# design.net
KiCad netlist of a schematic drawn in EasyEDA
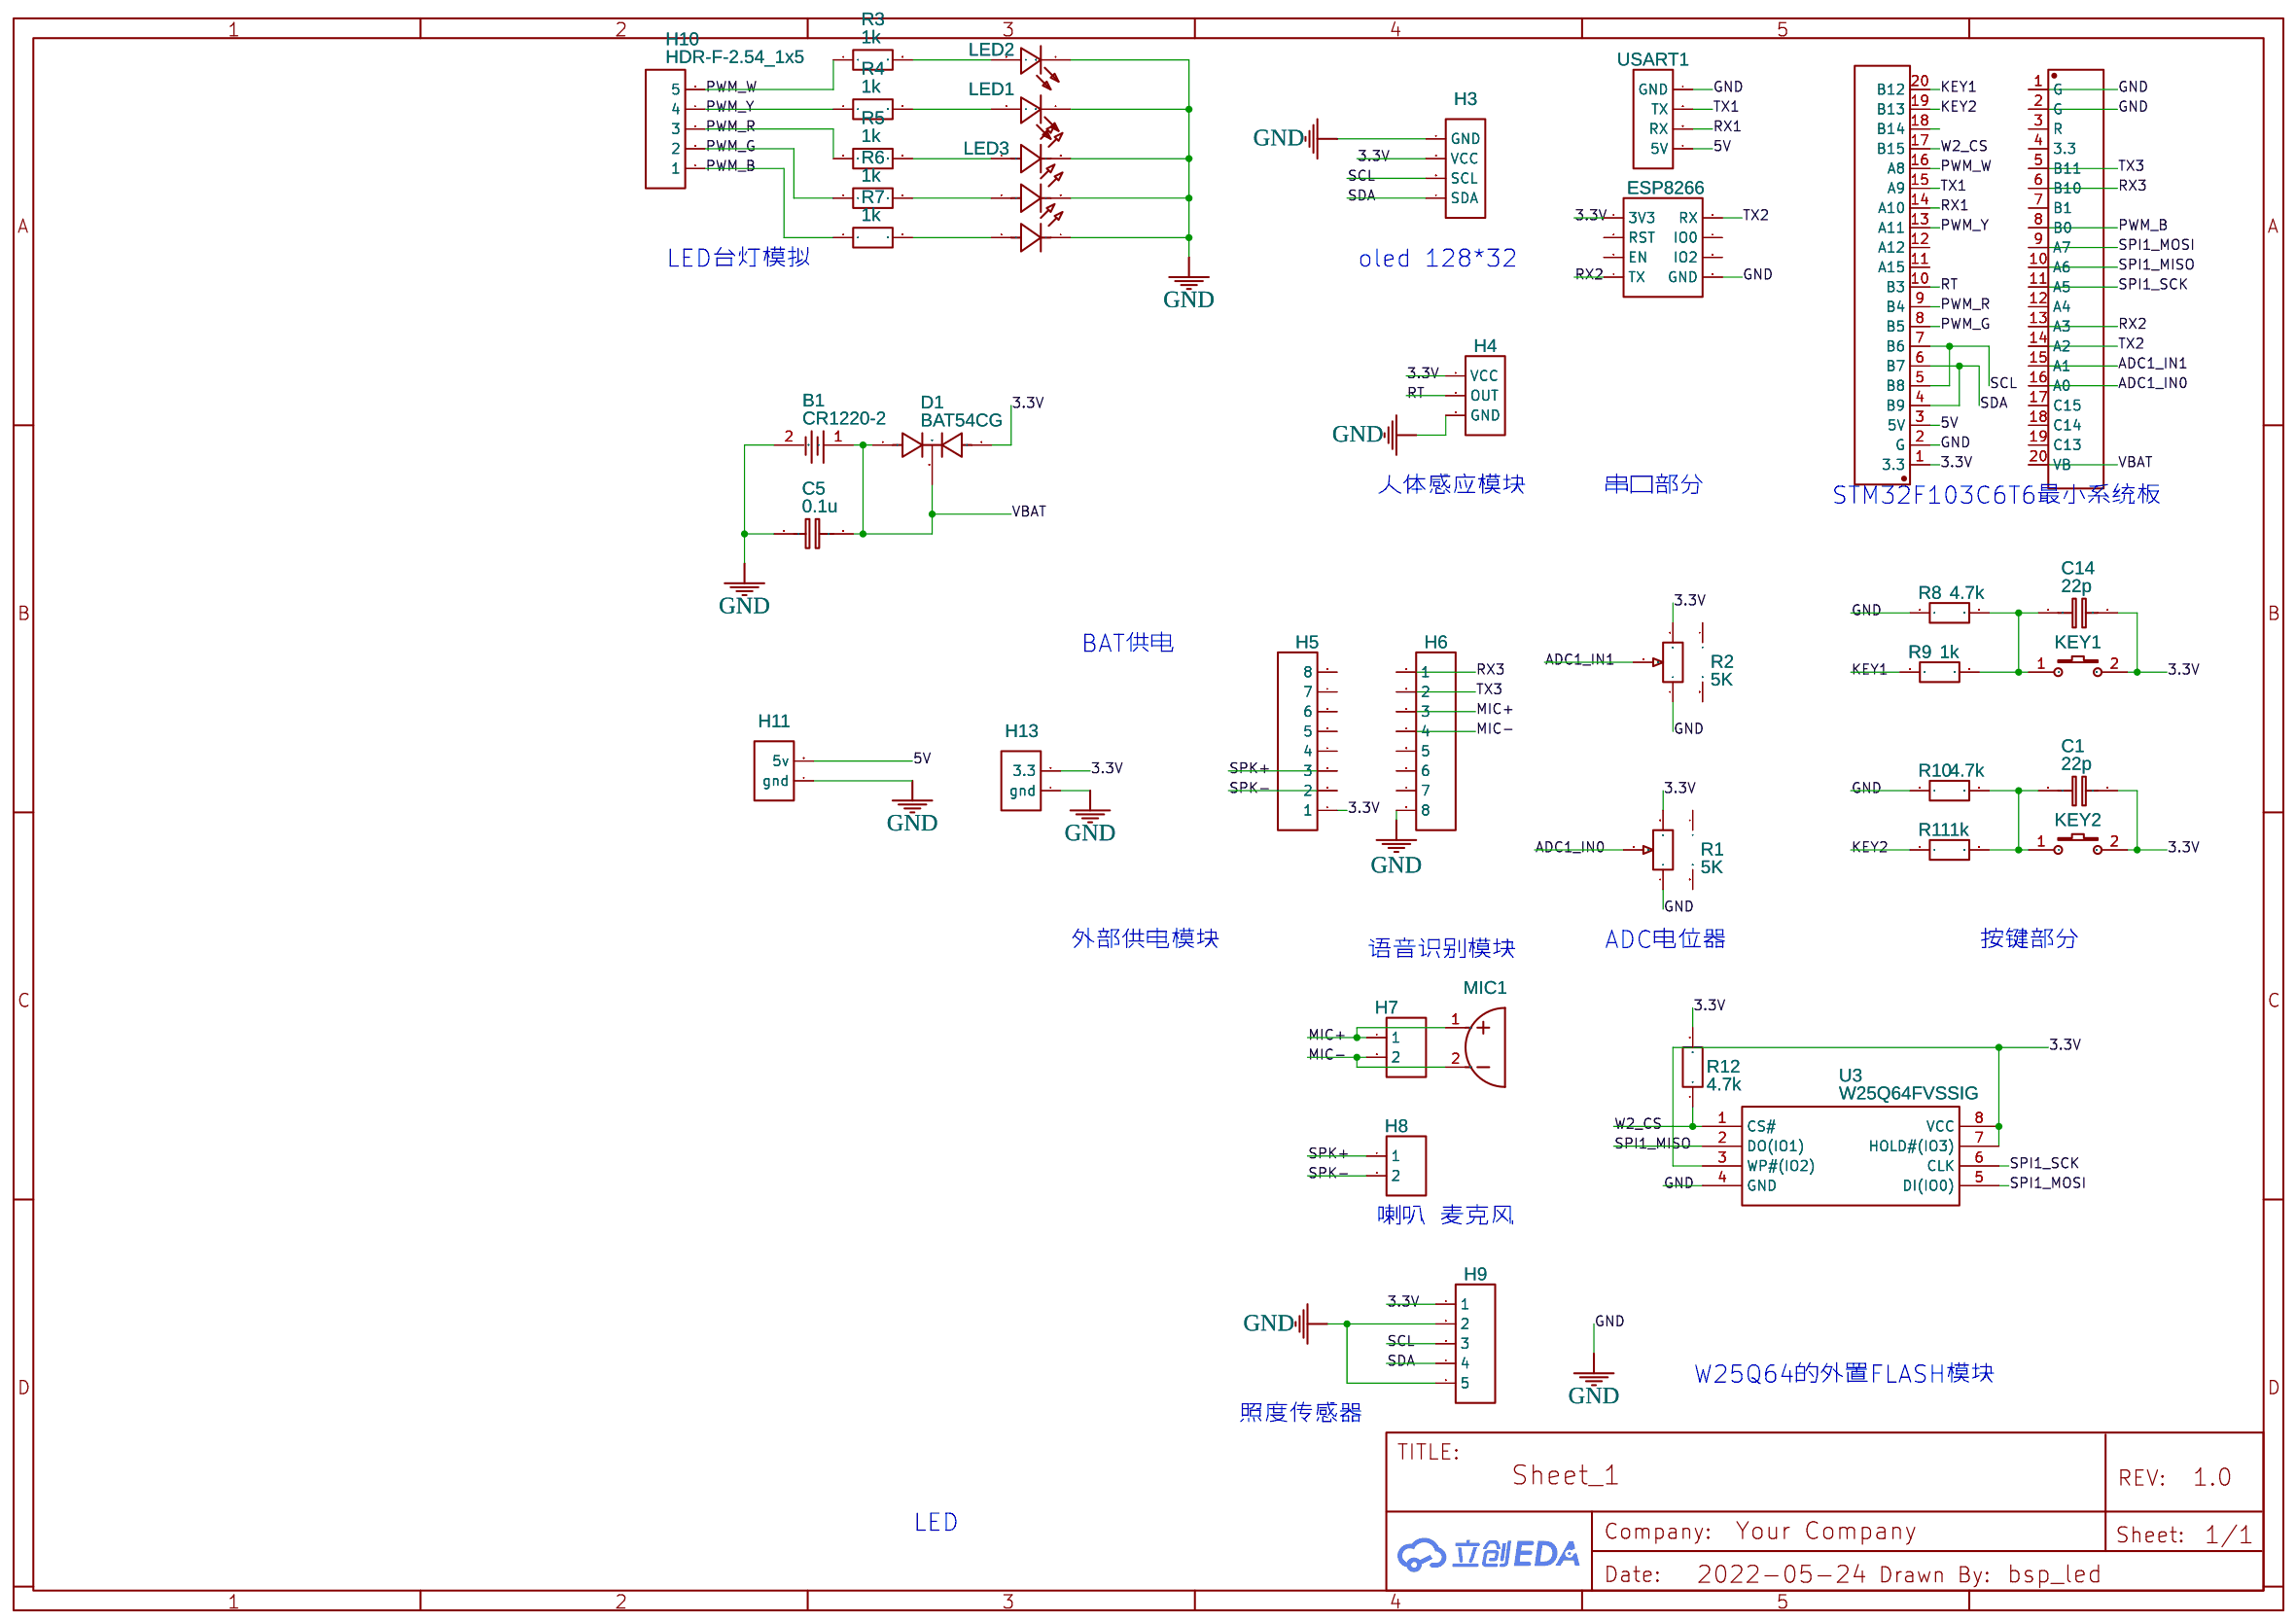
[diagram p0: schematic sheet]

(export (version "E")
  (design (tool "Eeschema 10.0.6"))
  (components
    (comp (ref "B1")
      (value "CR1220-2")
      (fields (field (name "BOM_Supplier Part") "C70381"))
      (libsource (lib "") (part "CR1220-2"))
    )
    (comp (ref "C1") (value "22p") (libsource (lib "") (part "C_1206_EU_2")))
    (comp (ref "C5") (value "0.1u") (libsource (lib "") (part "C_1206_EU_1")))
    (comp (ref "C14") (value "22p") (libsource (lib "") (part "C_1206_EU")))
    (comp (ref "D1")
      (value "BAT54CG")
      (fields (field (name "BOM_Supplier Part") "C393559"))
      (libsource (lib "") (part "BAT54CG"))
    )
    (comp (ref "ESP8266")
      (value "HDR-F-2.54_2x4")
      (fields (field (name "BOM_Supplier Part") "C239344"))
      (libsource (lib "") (part "HDR-F-2.54_2x4"))
    )
    (comp (ref "H1")
      (value "2")
      (fields
        (field (name "BOM_Manufacturer Part") "220S-1*20P H=8.5MM Ytype Gold-plated")
        (field (name "BOM_Supplier Part") "C124410")
      )
      (libsource (lib "") (part "220S-1*20P H=8.5MM Ytype Gold-plated"))
    )
    (comp (ref "H2")
      (value "1")
      (fields
        (field (name "BOM_Manufacturer Part") "220S-1*20P H=8.5MM Ytype Gold-plated")
        (field (name "BOM_Supplier Part") "C124410")
      )
      (libsource (lib "") (part "220S-1*20P H=8.5MM Ytype Gold-plated_1"))
    )
    (comp (ref "H3")
      (value "HDR-F-2.54_1x4")
      (fields (field (name "BOM_Supplier Part") "C225501"))
      (libsource (lib "") (part "HDR-F-2.54_1x4_1"))
    )
    (comp (ref "H4")
      (value "HDR-F-2.54_1x3")
      (fields (field (name "BOM_Supplier Part") "C146690"))
      (libsource (lib "") (part "HDR-F-2.54_1x3"))
    )
    (comp (ref "H5")
      (value "HDR-F-2.54_1x8")
      (fields (field (name "BOM_Supplier Part") "C225505"))
      (libsource (lib "") (part "HDR-F-2.54_1x8"))
    )
    (comp (ref "H6")
      (value "HDR-F-2.54_1x8")
      (fields (field (name "BOM_Supplier Part") "C225505"))
      (libsource (lib "") (part "HDR-F-2.54_1x8_1"))
    )
    (comp (ref "H7")
      (value "HDR-F-2.54_1x2")
      (fields (field (name "BOM_Supplier Part") "C49661"))
      (libsource (lib "") (part "HDR-F-2.54_1x2_1"))
    )
    (comp (ref "H8")
      (value "HDR-F-2.54_1x2")
      (fields (field (name "BOM_Supplier Part") "C49661"))
      (libsource (lib "") (part "HDR-F-2.54_1x2_1"))
    )
    (comp (ref "H9")
      (value "HDR-F-2.54_1x5")
      (fields (field (name "BOM_Supplier Part") "C50950"))
      (libsource (lib "") (part "HDR-F-2.54_1x5"))
    )
    (comp (ref "H10")
      (value "HDR-F-2.54_1x5")
      (fields (field (name "BOM_Supplier Part") "C50950"))
      (libsource (lib "") (part "HDR-F-2.54_1x5_1"))
    )
    (comp (ref "H11")
      (value "HDR-F-2.54_1x2")
      (fields (field (name "BOM_Supplier Part") "C49661"))
      (libsource (lib "") (part "HDR-F-2.54_1x2_2"))
    )
    (comp (ref "H13")
      (value "HDR-F-2.54_1x2")
      (fields (field (name "BOM_Supplier Part") "C49661"))
      (libsource (lib "") (part "HDR-F-2.54_1x2"))
    )
    (comp (ref "KEY1")
      (value "K2-3.6×6.1_SMD")
      (fields
        (field (name "BOM_Manufacturer Part") "K2-1107ST-A4SW-06")
        (field (name "BOM_Supplier Part") "C118141")
      )
      (libsource (lib "") (part "K2-3.6×6.1_SMD"))
    )
    (comp (ref "KEY2")
      (value "K2-3.6×6.1_SMD")
      (fields
        (field (name "BOM_Manufacturer Part") "K2-1107ST-A4SW-06")
        (field (name "BOM_Supplier Part") "C118141")
      )
      (libsource (lib "") (part "K2-3.6×6.1_SMD"))
    )
    (comp (ref "LED1")
      (value "2835正白光0.5W")
      (fields (field (name "BOM_Supplier Part") "C2895090"))
      (libsource (lib "") (part "2835正白光0.5W"))
    )
    (comp (ref "LED2")
      (value "2835正白光0.5W")
      (fields (field (name "BOM_Supplier Part") "C2895090"))
      (libsource (lib "") (part "2835正白光0.5W"))
    )
    (comp (ref "LED3")
      (value "TC5050RGBF08-3CJH-AF53A")
      (fields (field (name "BOM_Supplier Part") "C784540"))
      (libsource (lib "") (part "TC5050RGBF08-3CJH-AF53A"))
    )
    (comp (ref "MIC1")
      (value "GMI4015P-30DB")
      (fields (field (name "BOM_Supplier Part") "C529894"))
      (libsource (lib "") (part "GMI4015P-30DB"))
    )
    (comp (ref "R1")
      (value "5K")
      (fields
        (field (name "BOM_Manufacturer Part") "Potentiometer WH160-1-104")
        (field (name "BOM_Supplier Part") "C61836")
      )
      (libsource (lib "") (part "Potentiometer WH160-1-104"))
    )
    (comp (ref "R2")
      (value "5K")
      (fields
        (field (name "BOM_Manufacturer Part") "Potentiometer WH160-1-104")
        (field (name "BOM_Supplier Part") "C61836")
      )
      (libsource (lib "") (part "Potentiometer WH160-1-104"))
    )
    (comp (ref "R3") (value "1k") (libsource (lib "") (part "R_0805_EU_1")))
    (comp (ref "R4") (value "1k") (libsource (lib "") (part "R_0805_EU_1")))
    (comp (ref "R5") (value "1k") (libsource (lib "") (part "R_0805_EU_1")))
    (comp (ref "R6") (value "1k") (libsource (lib "") (part "R_0805_EU_1")))
    (comp (ref "R7") (value "1k") (libsource (lib "") (part "R_0805_EU_1")))
    (comp (ref "R8") (value "4.7k") (libsource (lib "") (part "R_0805_EU_1")))
    (comp (ref "R9") (value "1k") (libsource (lib "") (part "R_0805_EU_1")))
    (comp (ref "R10") (value "4.7k") (libsource (lib "") (part "R_0805_EU_1")))
    (comp (ref "R11") (value "1k") (libsource (lib "") (part "R_0805_EU_1")))
    (comp (ref "R12") (value "4.7k") (libsource (lib "") (part "R_0805_EU")))
    (comp (ref "U3")
      (value "W25Q64FVSSIG")
      (fields (field (name "BOM_Supplier Part") "C14067"))
      (libsource (lib "") (part "W25Q64FVSSIG"))
    )
    (comp (ref "USART1")
      (value "HDR-F-2.54_1x4")
      (fields (field (name "BOM_Supplier Part") "C225501"))
      (libsource (lib "") (part "HDR-F-2.54_1x4"))
    )
  )
  (nets
    (net (code "1") (name "/3.3V") (class "Default")
      (node (ref "C1") (pin "1") (pinfunction "1_1") (pintype "unspecified"))
      (node (ref "C14") (pin "1") (pinfunction "1_1") (pintype "unspecified"))
      (node (ref "D1") (pin "2") (pinfunction "A_2") (pintype "unspecified"))
      (node (ref "ESP8266") (pin "1") (pinfunction "3V3_1") (pintype "unspecified"))
      (node (ref "H13") (pin "2") (pinfunction "3.3_2") (pintype "input"))
      (node (ref "H2") (pin "1") (pinfunction "3.3_1") (pintype "unspecified"))
      (node (ref "H3") (pin "2") (pinfunction "VCC_2") (pintype "unspecified"))
      (node (ref "H4") (pin "1") (pinfunction "VCC_1") (pintype "input"))
      (node (ref "H5") (pin "1") (pinfunction "1_1") (pintype "unspecified"))
      (node (ref "H9") (pin "1") (pinfunction "1_1") (pintype "unspecified"))
      (node (ref "KEY1") (pin "2") (pinfunction "2_2") (pintype "unspecified"))
      (node (ref "KEY2") (pin "2") (pinfunction "2_2") (pintype "unspecified"))
      (node (ref "R1") (pin "3") (pinfunction "3_3") (pintype "input"))
      (node (ref "R12") (pin "2") (pinfunction "2_2") (pintype "unspecified"))
      (node (ref "R2") (pin "3") (pinfunction "3_3") (pintype "input"))
      (node (ref "U3") (pin "3") (pinfunction "WP#(IO2)_3") (pintype "unspecified"))
      (node (ref "U3") (pin "7") (pinfunction "HOLD#(IO3)_7") (pintype "unspecified"))
      (node (ref "U3") (pin "8") (pinfunction "VCC_8") (pintype "unspecified"))
    )
    (net (code "2") (name "/5V") (class "Default")
      (node (ref "H11") (pin "2") (pinfunction "5v_2") (pintype "input"))
      (node (ref "H2") (pin "3") (pinfunction "5V_3") (pintype "unspecified"))
      (node (ref "USART1") (pin "1") (pinfunction "5V_1") (pintype "unspecified"))
    )
    (net (code "3") (name "/ADC1_IN0") (class "Default")
      (node (ref "H1") (pin "16") (pinfunction "A0_16") (pintype "unspecified"))
      (node (ref "R1") (pin "2") (pinfunction "2_2") (pintype "input"))
    )
    (net (code "4") (name "/ADC1_IN1") (class "Default")
      (node (ref "H1") (pin "15") (pinfunction "A1_15") (pintype "unspecified"))
      (node (ref "R2") (pin "2") (pinfunction "2_2") (pintype "input"))
    )
    (net (code "5") (name "/KEY1") (class "Default")
      (node (ref "H2") (pin "20") (pinfunction "B12_20") (pintype "unspecified"))
      (node (ref "R9") (pin "1") (pinfunction "1_1") (pintype "unspecified"))
    )
    (net (code "6") (name "/KEY2") (class "Default")
      (node (ref "H2") (pin "19") (pinfunction "B13_19") (pintype "unspecified"))
      (node (ref "R11") (pin "1") (pinfunction "1_1") (pintype "unspecified"))
    )
    (net (code "7") (name "/MIC+") (class "Default")
      (node (ref "H6") (pin "3") (pinfunction "3_3") (pintype "unspecified"))
      (node (ref "H7") (pin "1") (pinfunction "1_1") (pintype "input"))
      (node (ref "MIC1") (pin "1") (pinfunction "1_1") (pintype "unspecified"))
    )
    (net (code "8") (name "/MIC-") (class "Default")
      (node (ref "H6") (pin "4") (pinfunction "4_4") (pintype "unspecified"))
      (node (ref "H7") (pin "2") (pinfunction "2_2") (pintype "input"))
      (node (ref "MIC1") (pin "2") (pinfunction "2_2") (pintype "unspecified"))
    )
    (net (code "9") (name "/PWM_B") (class "Default")
      (node (ref "H1") (pin "8") (pinfunction "B0_8") (pintype "unspecified"))
      (node (ref "H10") (pin "1") (pinfunction "1_1") (pintype "unspecified"))
      (node (ref "R7") (pin "1") (pinfunction "1_1") (pintype "unspecified"))
    )
    (net (code "10") (name "/PWM_G") (class "Default")
      (node (ref "H10") (pin "2") (pinfunction "2_2") (pintype "unspecified"))
      (node (ref "H2") (pin "8") (pinfunction "B5_8") (pintype "unspecified"))
      (node (ref "R6") (pin "1") (pinfunction "1_1") (pintype "unspecified"))
    )
    (net (code "11") (name "/PWM_R") (class "Default")
      (node (ref "H10") (pin "3") (pinfunction "3_3") (pintype "unspecified"))
      (node (ref "H2") (pin "9") (pinfunction "B4_9") (pintype "unspecified"))
      (node (ref "R5") (pin "1") (pinfunction "1_1") (pintype "unspecified"))
    )
    (net (code "12") (name "/PWM_W") (class "Default")
      (node (ref "H10") (pin "5") (pinfunction "5_5") (pintype "unspecified"))
      (node (ref "H2") (pin "16") (pinfunction "A8_16") (pintype "unspecified"))
      (node (ref "R3") (pin "1") (pinfunction "1_1") (pintype "unspecified"))
    )
    (net (code "13") (name "/PWM_Y") (class "Default")
      (node (ref "H10") (pin "4") (pinfunction "4_4") (pintype "unspecified"))
      (node (ref "H2") (pin "13") (pinfunction "A11_13") (pintype "unspecified"))
      (node (ref "R4") (pin "1") (pinfunction "1_1") (pintype "unspecified"))
    )
    (net (code "14") (name "/RT") (class "Default")
      (node (ref "H2") (pin "10") (pinfunction "B3_10") (pintype "unspecified"))
      (node (ref "H4") (pin "2") (pinfunction "OUT_2") (pintype "input"))
    )
    (net (code "15") (name "/RX1") (class "Default")
      (node (ref "H2") (pin "14") (pinfunction "A10_14") (pintype "unspecified"))
      (node (ref "USART1") (pin "2") (pinfunction "RX_2") (pintype "unspecified"))
    )
    (net (code "16") (name "/RX2") (class "Default")
      (node (ref "ESP8266") (pin "7") (pinfunction "TX_7") (pintype "unspecified"))
      (node (ref "H1") (pin "13") (pinfunction "A3_13") (pintype "unspecified"))
    )
    (net (code "17") (name "/RX3") (class "Default")
      (node (ref "H1") (pin "6") (pinfunction "B10_6") (pintype "unspecified"))
      (node (ref "H6") (pin "1") (pinfunction "1_1") (pintype "unspecified"))
    )
    (net (code "18") (name "/SCL") (class "Default")
      (node (ref "H2") (pin "5") (pinfunction "B8_5") (pintype "unspecified"))
      (node (ref "H2") (pin "7") (pinfunction "B6_7") (pintype "unspecified"))
      (node (ref "H3") (pin "3") (pinfunction "SCL_3") (pintype "unspecified"))
      (node (ref "H9") (pin "3") (pinfunction "3_3") (pintype "unspecified"))
    )
    (net (code "19") (name "/SDA") (class "Default")
      (node (ref "H2") (pin "4") (pinfunction "B9_4") (pintype "unspecified"))
      (node (ref "H2") (pin "6") (pinfunction "B7_6") (pintype "unspecified"))
      (node (ref "H3") (pin "4") (pinfunction "SDA_4") (pintype "unspecified"))
      (node (ref "H9") (pin "4") (pinfunction "4_4") (pintype "unspecified"))
    )
    (net (code "20") (name "/SPI1_MISO") (class "Default")
      (node (ref "H1") (pin "10") (pinfunction "A6_10") (pintype "unspecified"))
      (node (ref "U3") (pin "2") (pinfunction "DO(IO1)_2") (pintype "unspecified"))
    )
    (net (code "21") (name "/SPI1_MOSI") (class "Default")
      (node (ref "H1") (pin "9") (pinfunction "A7_9") (pintype "unspecified"))
      (node (ref "U3") (pin "5") (pinfunction "DI(IO0)_5") (pintype "unspecified"))
    )
    (net (code "22") (name "/SPI1_SCK") (class "Default")
      (node (ref "H1") (pin "11") (pinfunction "A5_11") (pintype "unspecified"))
      (node (ref "U3") (pin "6") (pinfunction "CLK_6") (pintype "unspecified"))
    )
    (net (code "23") (name "/SPK+") (class "Default")
      (node (ref "H5") (pin "3") (pinfunction "3_3") (pintype "unspecified"))
      (node (ref "H8") (pin "1") (pinfunction "1_1") (pintype "input"))
    )
    (net (code "24") (name "/SPK-") (class "Default")
      (node (ref "H5") (pin "2") (pinfunction "2_2") (pintype "unspecified"))
      (node (ref "H8") (pin "2") (pinfunction "2_2") (pintype "input"))
    )
    (net (code "25") (name "/TX1") (class "Default")
      (node (ref "H2") (pin "15") (pinfunction "A9_15") (pintype "unspecified"))
      (node (ref "USART1") (pin "3") (pinfunction "TX_3") (pintype "unspecified"))
    )
    (net (code "26") (name "/TX2") (class "Default")
      (node (ref "ESP8266") (pin "2") (pinfunction "RX_2") (pintype "unspecified"))
      (node (ref "H1") (pin "14") (pinfunction "A2_14") (pintype "unspecified"))
    )
    (net (code "27") (name "/TX3") (class "Default")
      (node (ref "H1") (pin "5") (pinfunction "B11_5") (pintype "unspecified"))
      (node (ref "H6") (pin "2") (pinfunction "2_2") (pintype "unspecified"))
    )
    (net (code "28") (name "/VBAT") (class "Default")
      (node (ref "B1") (pin "1") (pinfunction "1_1") (pintype "input"))
      (node (ref "C5") (pin "2") (pinfunction "2_2") (pintype "unspecified"))
      (node (ref "D1") (pin "1") (pinfunction "A_1") (pintype "unspecified"))
      (node (ref "D1") (pin "3") (pinfunction "C_3") (pintype "unspecified"))
      (node (ref "H1") (pin "20") (pinfunction "VB_20") (pintype "unspecified"))
    )
    (net (code "29") (name "/W2_CS") (class "Default")
      (node (ref "H2") (pin "17") (pinfunction "B15_17") (pintype "unspecified"))
      (node (ref "R12") (pin "1") (pinfunction "1_1") (pintype "unspecified"))
      (node (ref "U3") (pin "1") (pinfunction "CS#_1") (pintype "unspecified"))
    )
    (net (code "30") (name "GND") (class "Default")
      (node (ref "B1") (pin "2") (pinfunction "2_2") (pintype "input"))
      (node (ref "C5") (pin "1") (pinfunction "1_1") (pintype "unspecified"))
      (node (ref "ESP8266") (pin "8") (pinfunction "GND_8") (pintype "unspecified"))
      (node (ref "H1") (pin "1") (pinfunction "G_1") (pintype "unspecified"))
      (node (ref "H1") (pin "2") (pinfunction "G_2") (pintype "unspecified"))
      (node (ref "H11") (pin "1") (pinfunction "gnd_1") (pintype "input"))
      (node (ref "H13") (pin "1") (pinfunction "gnd_1") (pintype "input"))
      (node (ref "H2") (pin "2") (pinfunction "G_2") (pintype "unspecified"))
      (node (ref "H3") (pin "1") (pinfunction "GND_1") (pintype "unspecified"))
      (node (ref "H4") (pin "3") (pinfunction "GND_3") (pintype "input"))
      (node (ref "H6") (pin "8") (pinfunction "8_8") (pintype "unspecified"))
      (node (ref "H9") (pin "2") (pinfunction "2_2") (pintype "unspecified"))
      (node (ref "H9") (pin "5") (pinfunction "5_5") (pintype "unspecified"))
      (node (ref "LED1") (pin "1") (pinfunction "C_1") (pintype "unspecified"))
      (node (ref "LED2") (pin "1") (pinfunction "C_1") (pintype "unspecified"))
      (node (ref "LED3") (pin "4") (pinfunction "-_4") (pintype "unspecified"))
      (node (ref "LED3") (pin "5") (pinfunction "-_5") (pintype "unspecified"))
      (node (ref "LED3") (pin "6") (pinfunction "-_6") (pintype "unspecified"))
      (node (ref "R1") (pin "1") (pinfunction "1_1") (pintype "input"))
      (node (ref "R10") (pin "1") (pinfunction "1_1") (pintype "unspecified"))
      (node (ref "R2") (pin "1") (pinfunction "1_1") (pintype "input"))
      (node (ref "R8") (pin "1") (pinfunction "1_1") (pintype "unspecified"))
      (node (ref "U3") (pin "4") (pinfunction "GND_4") (pintype "unspecified"))
      (node (ref "USART1") (pin "4") (pinfunction "GND_4") (pintype "unspecified"))
    )
    (net (code "31") (name "Net-(C1-Pad2)") (class "Default")
      (node (ref "C1") (pin "2") (pinfunction "2_2") (pintype "unspecified"))
      (node (ref "KEY2") (pin "1") (pinfunction "1_1") (pintype "unspecified"))
      (node (ref "R10") (pin "2") (pinfunction "2_2") (pintype "unspecified"))
      (node (ref "R11") (pin "2") (pinfunction "2_2") (pintype "unspecified"))
    )
    (net (code "32") (name "Net-(C14-Pad2)") (class "Default")
      (node (ref "C14") (pin "2") (pinfunction "2_2") (pintype "unspecified"))
      (node (ref "KEY1") (pin "1") (pinfunction "1_1") (pintype "unspecified"))
      (node (ref "R8") (pin "2") (pinfunction "2_2") (pintype "unspecified"))
      (node (ref "R9") (pin "2") (pinfunction "2_2") (pintype "unspecified"))
    )
    (net (code "33") (name "Net-(LED1-A)") (class "Default")
      (node (ref "LED1") (pin "2") (pinfunction "A_2") (pintype "unspecified"))
      (node (ref "R4") (pin "2") (pinfunction "2_2") (pintype "unspecified"))
    )
    (net (code "34") (name "Net-(LED2-A)") (class "Default")
      (node (ref "LED2") (pin "2") (pinfunction "A_2") (pintype "unspecified"))
      (node (ref "R3") (pin "2") (pinfunction "2_2") (pintype "unspecified"))
    )
    (net (code "35") (name "Net-(LED3-+-Pad1)") (class "Default")
      (node (ref "LED3") (pin "1") (pinfunction "+_1") (pintype "unspecified"))
      (node (ref "R5") (pin "2") (pinfunction "2_2") (pintype "unspecified"))
    )
    (net (code "36") (name "Net-(LED3-+-Pad2)") (class "Default")
      (node (ref "LED3") (pin "2") (pinfunction "+_2") (pintype "unspecified"))
      (node (ref "R6") (pin "2") (pinfunction "2_2") (pintype "unspecified"))
    )
    (net (code "37") (name "Net-(LED3-+-Pad3)") (class "Default")
      (node (ref "LED3") (pin "3") (pinfunction "+_3") (pintype "unspecified"))
      (node (ref "R7") (pin "2") (pinfunction "2_2") (pintype "unspecified"))
    )
    (net (code "38") (name "unconnected-(ESP8266-EN-Pad5)") (class "Default")
      (node (ref "ESP8266") (pin "5") (pinfunction "EN_5") (pintype "unspecified"))
    )
    (net (code "39") (name "unconnected-(ESP8266-IO0-Pad4)") (class "Default")
      (node (ref "ESP8266") (pin "4") (pinfunction "IO0_4") (pintype "unspecified"))
    )
    (net (code "40") (name "unconnected-(ESP8266-IO2-Pad6)") (class "Default")
      (node (ref "ESP8266") (pin "6") (pinfunction "IO2_6") (pintype "unspecified"))
    )
    (net (code "41") (name "unconnected-(ESP8266-RST-Pad3)") (class "Default")
      (node (ref "ESP8266") (pin "3") (pinfunction "RST_3") (pintype "unspecified"))
    )
    (net (code "42") (name "unconnected-(H1-3.3-Pad4)") (class "Default")
      (node (ref "H1") (pin "4") (pinfunction "3.3_4") (pintype "unspecified"))
    )
    (net (code "43") (name "unconnected-(H1-A4-Pad12)") (class "Default")
      (node (ref "H1") (pin "12") (pinfunction "A4_12") (pintype "unspecified"))
    )
    (net (code "44") (name "unconnected-(H1-B1-Pad7)") (class "Default")
      (node (ref "H1") (pin "7") (pinfunction "B1_7") (pintype "unspecified"))
    )
    (net (code "45") (name "unconnected-(H1-C13-Pad19)") (class "Default")
      (node (ref "H1") (pin "19") (pinfunction "C13_19") (pintype "unspecified"))
    )
    (net (code "46") (name "unconnected-(H1-C14-Pad18)") (class "Default")
      (node (ref "H1") (pin "18") (pinfunction "C14_18") (pintype "unspecified"))
    )
    (net (code "47") (name "unconnected-(H1-C15-Pad17)") (class "Default")
      (node (ref "H1") (pin "17") (pinfunction "C15_17") (pintype "unspecified"))
    )
    (net (code "48") (name "unconnected-(H1-R-Pad3)") (class "Default")
      (node (ref "H1") (pin "3") (pinfunction "R_3") (pintype "unspecified"))
    )
    (net (code "49") (name "unconnected-(H2-A12-Pad12)") (class "Default")
      (node (ref "H2") (pin "12") (pinfunction "A12_12") (pintype "unspecified"))
    )
    (net (code "50") (name "unconnected-(H2-A15-Pad11)") (class "Default")
      (node (ref "H2") (pin "11") (pinfunction "A15_11") (pintype "unspecified"))
    )
    (net (code "51") (name "unconnected-(H2-B14-Pad18)") (class "Default")
      (node (ref "H2") (pin "18") (pinfunction "B14_18") (pintype "unspecified"))
    )
    (net (code "52") (name "unconnected-(H5-Pad4)") (class "Default")
      (node (ref "H5") (pin "4") (pinfunction "4_4") (pintype "unspecified"))
    )
    (net (code "53") (name "unconnected-(H5-Pad5)") (class "Default")
      (node (ref "H5") (pin "5") (pinfunction "5_5") (pintype "unspecified"))
    )
    (net (code "54") (name "unconnected-(H5-Pad6)") (class "Default")
      (node (ref "H5") (pin "6") (pinfunction "6_6") (pintype "unspecified"))
    )
    (net (code "55") (name "unconnected-(H5-Pad7)") (class "Default")
      (node (ref "H5") (pin "7") (pinfunction "7_7") (pintype "unspecified"))
    )
    (net (code "56") (name "unconnected-(H5-Pad8)") (class "Default")
      (node (ref "H5") (pin "8") (pinfunction "8_8") (pintype "unspecified"))
    )
    (net (code "57") (name "unconnected-(H6-Pad5)") (class "Default")
      (node (ref "H6") (pin "5") (pinfunction "5_5") (pintype "unspecified"))
    )
    (net (code "58") (name "unconnected-(H6-Pad6)") (class "Default")
      (node (ref "H6") (pin "6") (pinfunction "6_6") (pintype "unspecified"))
    )
    (net (code "59") (name "unconnected-(H6-Pad7)") (class "Default")
      (node (ref "H6") (pin "7") (pinfunction "7_7") (pintype "unspecified"))
    )
    (net (code "60") (name "unconnected-(R1-Pad4)") (class "Default")
      (node (ref "R1") (pin "4") (pinfunction "4_4") (pintype "input"))
    )
    (net (code "61") (name "unconnected-(R1-Pad5)") (class "Default")
      (node (ref "R1") (pin "5") (pinfunction "5_5") (pintype "input"))
    )
    (net (code "62") (name "unconnected-(R2-Pad4)") (class "Default")
      (node (ref "R2") (pin "4") (pinfunction "4_4") (pintype "input"))
    )
    (net (code "63") (name "unconnected-(R2-Pad5)") (class "Default")
      (node (ref "R2") (pin "5") (pinfunction "5_5") (pintype "input"))
    )
  )
)
